# Touch.net
KiCad netlist of a schematic drawn in Altium Designer
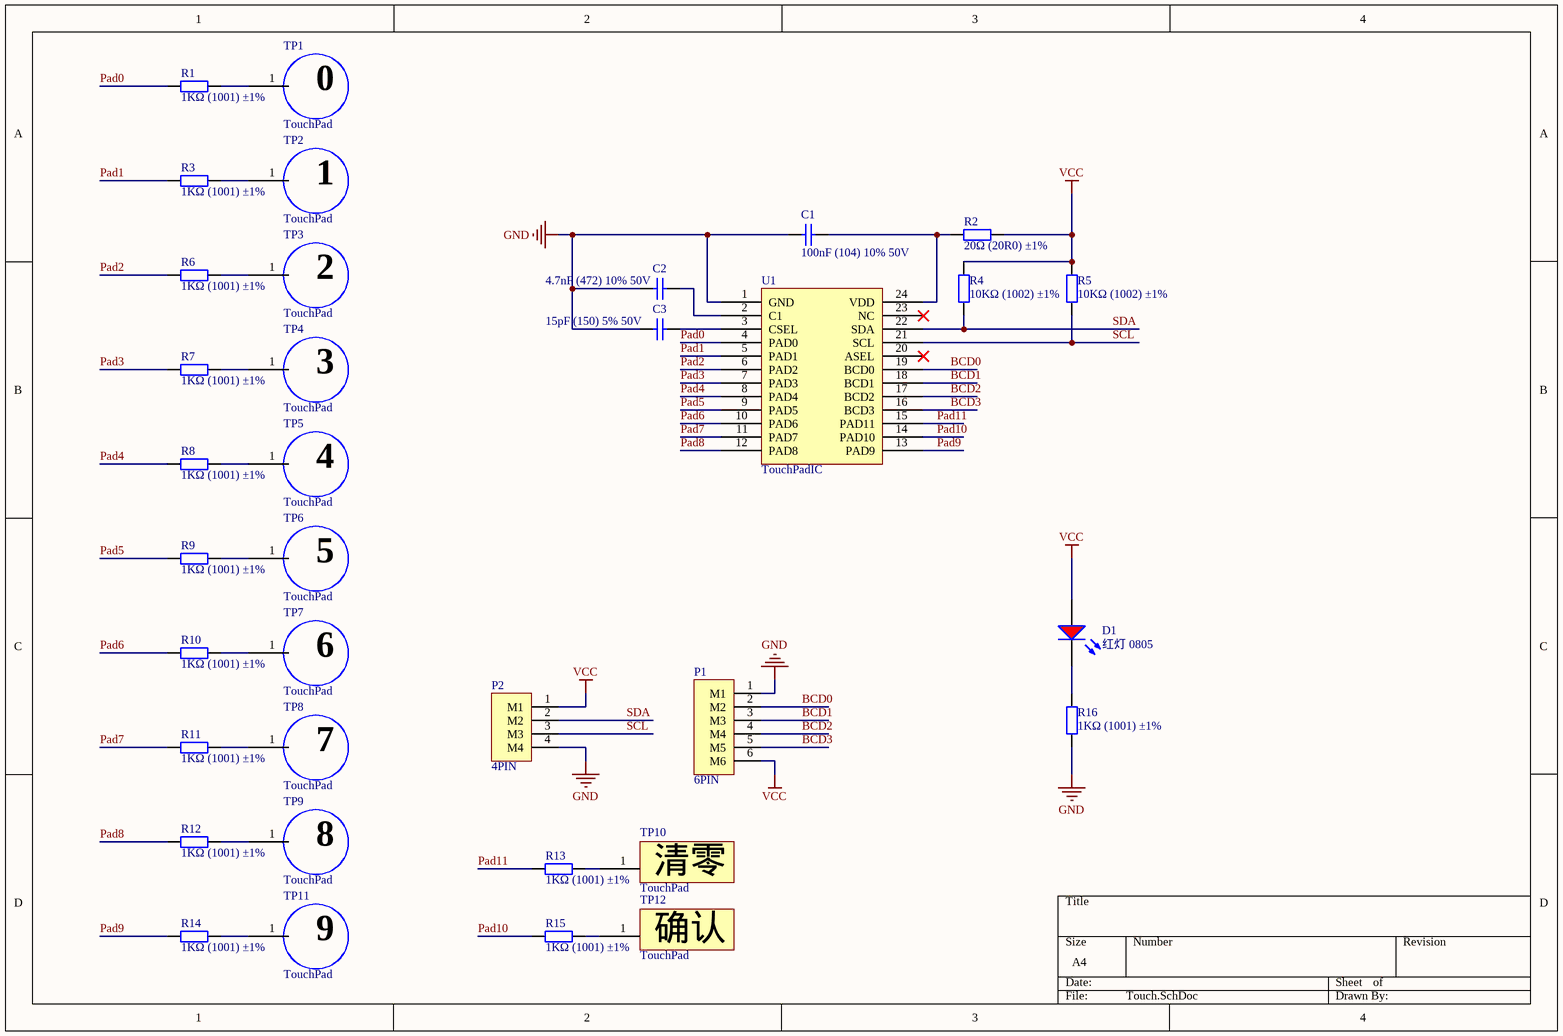
[diagram p0: Touch.SchDoc]

(export (version "E")
  (design (tool "Eeschema 10.0.6"))
  (components
    (comp (ref "C1")
      (value "100nF (104) 10% 50V")
      (footprint "0603_C")
      (description "贴片电容")
      (libsource (lib "Cap") (part "0603 100nF (104) 10% 50V"))
    )
    (comp (ref "C2")
      (value "4.7nF (472) 10% 50V")
      (footprint "0603_C")
      (description "贴片电容")
      (libsource (lib "Cap") (part "0603 4.7nF (472) 10% 50V"))
    )
    (comp (ref "C3")
      (value "15pF (150) 5% 50V")
      (footprint "0603_C")
      (description "贴片电容")
      (libsource (lib "Cap") (part "0603 15pF (150) 5% 50V"))
    )
    (comp (ref "D1")
      (value "红灯 0805")
      (footprint "0805_LED_S1")
      (description "发光二极管")
      (libsource (lib "LED") (part "0805 红灯"))
    )
    (comp (ref "P1") (value "6PIN") (footprint "MX1.25WS-6P") (libsource (lib "集大电协1.5") (part "接线端子-6PIN")))
    (comp (ref "P2") (value "4PIN") (footprint "PH2.0WS-4P") (libsource (lib "集大电协1.5") (part "接线端子-4PIN")))
    (comp (ref "R1")
      (value "1KΩ (1001) ±1%")
      (footprint "0603_R")
      (description "贴片电阻")
      (libsource (lib "RES") (part "0603 1KΩ (1001) 1%"))
    )
    (comp (ref "R2")
      (value "20Ω (20R0) ±1%")
      (footprint "0603_R")
      (description "贴片电阻")
      (libsource (lib "RES") (part "0603 20Ω (20R0) 1%"))
    )
    (comp (ref "R3")
      (value "1KΩ (1001) ±1%")
      (footprint "0603_R")
      (description "贴片电阻")
      (libsource (lib "RES") (part "0603 1KΩ (1001) 1%"))
    )
    (comp (ref "R4")
      (value "10KΩ (1002) ±1%")
      (footprint "0603_R")
      (description "贴片电阻")
      (libsource (lib "RES") (part "0603 10KΩ (1002) 1%"))
    )
    (comp (ref "R5")
      (value "10KΩ (1002) ±1%")
      (footprint "0603_R")
      (description "贴片电阻")
      (libsource (lib "RES") (part "0603 10KΩ (1002) 1%"))
    )
    (comp (ref "R6")
      (value "1KΩ (1001) ±1%")
      (footprint "0603_R")
      (description "贴片电阻")
      (libsource (lib "RES") (part "0603 1KΩ (1001) 1%"))
    )
    (comp (ref "R7")
      (value "1KΩ (1001) ±1%")
      (footprint "0603_R")
      (description "贴片电阻")
      (libsource (lib "RES") (part "0603 1KΩ (1001) 1%"))
    )
    (comp (ref "R8")
      (value "1KΩ (1001) ±1%")
      (footprint "0603_R")
      (description "贴片电阻")
      (libsource (lib "RES") (part "0603 1KΩ (1001) 1%"))
    )
    (comp (ref "R9")
      (value "1KΩ (1001) ±1%")
      (footprint "0603_R")
      (description "贴片电阻")
      (libsource (lib "RES") (part "0603 1KΩ (1001) 1%"))
    )
    (comp (ref "R10")
      (value "1KΩ (1001) ±1%")
      (footprint "0603_R")
      (description "贴片电阻")
      (libsource (lib "RES") (part "0603 1KΩ (1001) 1%"))
    )
    (comp (ref "R11")
      (value "1KΩ (1001) ±1%")
      (footprint "0603_R")
      (description "贴片电阻")
      (libsource (lib "RES") (part "0603 1KΩ (1001) 1%"))
    )
    (comp (ref "R12")
      (value "1KΩ (1001) ±1%")
      (footprint "0603_R")
      (description "贴片电阻")
      (libsource (lib "RES") (part "0603 1KΩ (1001) 1%"))
    )
    (comp (ref "R13")
      (value "1KΩ (1001) ±1%")
      (footprint "0603_R")
      (description "贴片电阻")
      (libsource (lib "RES") (part "0603 1KΩ (1001) 1%"))
    )
    (comp (ref "R14")
      (value "1KΩ (1001) ±1%")
      (footprint "0603_R")
      (description "贴片电阻")
      (libsource (lib "RES") (part "0603 1KΩ (1001) 1%"))
    )
    (comp (ref "R15")
      (value "1KΩ (1001) ±1%")
      (footprint "0603_R")
      (description "贴片电阻")
      (libsource (lib "RES") (part "0603 1KΩ (1001) 1%"))
    )
    (comp (ref "R16")
      (value "1KΩ (1001) ±1%")
      (footprint "0603_R")
      (description "贴片电阻")
      (libsource (lib "") (part "0603 1KΩ (1001) 1%_1"))
    )
    (comp (ref "TP1") (value "TouchPad") (footprint "KEY0") (libsource (lib "Schlib2") (part "Touch0")))
    (comp (ref "TP2") (value "TouchPad") (footprint "Key1") (libsource (lib "Schlib2") (part "Touch1")))
    (comp (ref "TP3") (value "TouchPad") (footprint "Key2") (libsource (lib "Schlib2") (part "Touch2")))
    (comp (ref "TP4") (value "TouchPad") (footprint "Key3") (libsource (lib "Schlib2") (part "Touch3")))
    (comp (ref "TP5") (value "TouchPad") (footprint "KEY4") (libsource (lib "Schlib2") (part "Touch4")))
    (comp (ref "TP6") (value "TouchPad") (footprint "KEY5") (libsource (lib "Schlib2") (part "Touch5")))
    (comp (ref "TP7") (value "TouchPad") (footprint "KEY6") (libsource (lib "Schlib2") (part "Touch6")))
    (comp (ref "TP8") (value "TouchPad") (footprint "KEY7") (libsource (lib "Schlib2") (part "Touch7")))
    (comp (ref "TP9") (value "TouchPad") (footprint "KEY8") (libsource (lib "Schlib2") (part "Touch8")))
    (comp (ref "TP10") (value "TouchPad") (footprint "CANCEL") (libsource (lib "Schlib2") (part "No")))
    (comp (ref "TP11") (value "TouchPad") (footprint "KEY9") (libsource (lib "Schlib2") (part "Touch9")))
    (comp (ref "TP12") (value "TouchPad") (footprint "confirm") (libsource (lib "Schlib2") (part "Yes")))
    (comp (ref "U1")
      (value "TouchPadIC")
      (footprint "SOP127P1030X264-24N")
      (libsource (lib "Schlib2") (part "XW12C"))
    )
  )
  (nets
    (net (code "1") (name "/BCD0") (class "Default")
      (node (ref "P1") (pin "2") (pinfunction "M2_2") (pintype "passive"))
      (node (ref "U1") (pin "19") (pinfunction "BCD0_19") (pintype "passive"))
    )
    (net (code "2") (name "/BCD1") (class "Default")
      (node (ref "P1") (pin "3") (pinfunction "M3_3") (pintype "passive"))
      (node (ref "U1") (pin "18") (pinfunction "BCD1_18") (pintype "passive"))
    )
    (net (code "3") (name "/BCD2") (class "Default")
      (node (ref "P1") (pin "4") (pinfunction "M4_4") (pintype "passive"))
      (node (ref "U1") (pin "17") (pinfunction "BCD2_17") (pintype "passive"))
    )
    (net (code "4") (name "/BCD3") (class "Default")
      (node (ref "P1") (pin "5") (pinfunction "M5_5") (pintype "passive"))
      (node (ref "U1") (pin "16") (pinfunction "BCD3_16") (pintype "passive"))
    )
    (net (code "5") (name "/Pad0") (class "Default")
      (node (ref "R1") (pin "1") (pinfunction "1_1") (pintype "passive"))
      (node (ref "U1") (pin "4") (pinfunction "PAD0_4") (pintype "passive"))
    )
    (net (code "6") (name "/Pad1") (class "Default")
      (node (ref "R3") (pin "1") (pinfunction "1_1") (pintype "passive"))
      (node (ref "U1") (pin "5") (pinfunction "PAD1_5") (pintype "passive"))
    )
    (net (code "7") (name "/Pad2") (class "Default")
      (node (ref "R6") (pin "1") (pinfunction "1_1") (pintype "passive"))
      (node (ref "U1") (pin "6") (pinfunction "PAD2_6") (pintype "passive"))
    )
    (net (code "8") (name "/Pad3") (class "Default")
      (node (ref "R7") (pin "1") (pinfunction "1_1") (pintype "passive"))
      (node (ref "U1") (pin "7") (pinfunction "PAD3_7") (pintype "passive"))
    )
    (net (code "9") (name "/Pad4") (class "Default")
      (node (ref "R8") (pin "1") (pinfunction "1_1") (pintype "passive"))
      (node (ref "U1") (pin "8") (pinfunction "PAD4_8") (pintype "passive"))
    )
    (net (code "10") (name "/Pad5") (class "Default")
      (node (ref "R9") (pin "1") (pinfunction "1_1") (pintype "passive"))
      (node (ref "U1") (pin "9") (pinfunction "PAD5_9") (pintype "passive"))
    )
    (net (code "11") (name "/Pad6") (class "Default")
      (node (ref "R10") (pin "1") (pinfunction "1_1") (pintype "passive"))
      (node (ref "U1") (pin "10") (pinfunction "PAD6_10") (pintype "passive"))
    )
    (net (code "12") (name "/Pad7") (class "Default")
      (node (ref "R11") (pin "1") (pinfunction "1_1") (pintype "passive"))
      (node (ref "U1") (pin "11") (pinfunction "PAD7_11") (pintype "passive"))
    )
    (net (code "13") (name "/Pad8") (class "Default")
      (node (ref "R12") (pin "1") (pinfunction "1_1") (pintype "passive"))
      (node (ref "U1") (pin "12") (pinfunction "PAD8_12") (pintype "passive"))
    )
    (net (code "14") (name "/Pad9") (class "Default")
      (node (ref "R14") (pin "1") (pinfunction "1_1") (pintype "passive"))
      (node (ref "U1") (pin "13") (pinfunction "PAD9_13") (pintype "passive"))
    )
    (net (code "15") (name "/Pad10") (class "Default")
      (node (ref "R15") (pin "1") (pinfunction "1_1") (pintype "passive"))
      (node (ref "U1") (pin "14") (pinfunction "PAD10_14") (pintype "passive"))
    )
    (net (code "16") (name "/Pad11") (class "Default")
      (node (ref "R13") (pin "1") (pinfunction "1_1") (pintype "passive"))
      (node (ref "U1") (pin "15") (pinfunction "PAD11_15") (pintype "passive"))
    )
    (net (code "17") (name "/SCL") (class "Default")
      (node (ref "P2") (pin "3") (pinfunction "M3_3") (pintype "passive"))
      (node (ref "R5") (pin "1") (pinfunction "1_1") (pintype "passive"))
      (node (ref "U1") (pin "21") (pinfunction "SCL_21") (pintype "passive"))
    )
    (net (code "18") (name "/SDA") (class "Default")
      (node (ref "P2") (pin "2") (pinfunction "M2_2") (pintype "passive"))
      (node (ref "R4") (pin "1") (pinfunction "1_1") (pintype "passive"))
      (node (ref "U1") (pin "22") (pinfunction "SDA_22") (pintype "passive"))
    )
    (net (code "19") (name "GND") (class "Default")
      (node (ref "C1") (pin "1") (pinfunction "1_1") (pintype "passive"))
      (node (ref "C2") (pin "1") (pinfunction "1_1") (pintype "passive"))
      (node (ref "C3") (pin "2") (pinfunction "2_2") (pintype "passive"))
      (node (ref "P1") (pin "1") (pinfunction "M1_1") (pintype "passive"))
      (node (ref "P2") (pin "4") (pinfunction "M4_4") (pintype "passive"))
      (node (ref "R16") (pin "1") (pinfunction "1_1") (pintype "passive"))
      (node (ref "U1") (pin "1") (pinfunction "GND_1") (pintype "passive"))
    )
    (net (code "20") (name "Net-(D1-PadK)") (class "Default")
      (node (ref "D1") (pin "K") (pinfunction "K_K") (pintype "passive"))
      (node (ref "R16") (pin "2") (pinfunction "2_2") (pintype "passive"))
    )
    (net (code "21") (name "Net-(R1-Pad2)") (class "Default")
      (node (ref "R1") (pin "2") (pinfunction "2_2") (pintype "passive"))
      (node (ref "TP1") (pin "1") (pinfunction "1_1") (pintype "passive"))
    )
    (net (code "22") (name "Net-(R3-Pad2)") (class "Default")
      (node (ref "R3") (pin "2") (pinfunction "2_2") (pintype "passive"))
      (node (ref "TP2") (pin "1") (pinfunction "1_1") (pintype "passive"))
    )
    (net (code "23") (name "Net-(R6-Pad2)") (class "Default")
      (node (ref "R6") (pin "2") (pinfunction "2_2") (pintype "passive"))
      (node (ref "TP3") (pin "1") (pinfunction "1_1") (pintype "passive"))
    )
    (net (code "24") (name "Net-(R7-Pad2)") (class "Default")
      (node (ref "R7") (pin "2") (pinfunction "2_2") (pintype "passive"))
      (node (ref "TP4") (pin "1") (pinfunction "1_1") (pintype "passive"))
    )
    (net (code "25") (name "Net-(R8-Pad2)") (class "Default")
      (node (ref "R8") (pin "2") (pinfunction "2_2") (pintype "passive"))
      (node (ref "TP5") (pin "1") (pinfunction "1_1") (pintype "passive"))
    )
    (net (code "26") (name "Net-(R9-Pad2)") (class "Default")
      (node (ref "R9") (pin "2") (pinfunction "2_2") (pintype "passive"))
      (node (ref "TP6") (pin "1") (pinfunction "1_1") (pintype "passive"))
    )
    (net (code "27") (name "Net-(R10-Pad2)") (class "Default")
      (node (ref "R10") (pin "2") (pinfunction "2_2") (pintype "passive"))
      (node (ref "TP7") (pin "1") (pinfunction "1_1") (pintype "passive"))
    )
    (net (code "28") (name "Net-(R11-Pad2)") (class "Default")
      (node (ref "R11") (pin "2") (pinfunction "2_2") (pintype "passive"))
      (node (ref "TP8") (pin "1") (pinfunction "1_1") (pintype "passive"))
    )
    (net (code "29") (name "Net-(R12-Pad2)") (class "Default")
      (node (ref "R12") (pin "2") (pinfunction "2_2") (pintype "passive"))
      (node (ref "TP9") (pin "1") (pinfunction "1_1") (pintype "passive"))
    )
    (net (code "30") (name "Net-(R13-Pad2)") (class "Default")
      (node (ref "R13") (pin "2") (pinfunction "2_2") (pintype "passive"))
      (node (ref "TP10") (pin "1") (pinfunction "1_1") (pintype "passive"))
    )
    (net (code "31") (name "Net-(R14-Pad2)") (class "Default")
      (node (ref "R14") (pin "2") (pinfunction "2_2") (pintype "passive"))
      (node (ref "TP11") (pin "1") (pinfunction "1_1") (pintype "passive"))
    )
    (net (code "32") (name "Net-(R15-Pad2)") (class "Default")
      (node (ref "R15") (pin "2") (pinfunction "2_2") (pintype "passive"))
      (node (ref "TP12") (pin "1") (pinfunction "1_1") (pintype "passive"))
    )
    (net (code "33") (name "Net-(U1-C1)") (class "Default")
      (node (ref "C2") (pin "2") (pinfunction "2_2") (pintype "passive"))
      (node (ref "U1") (pin "2") (pinfunction "C1_2") (pintype "passive"))
    )
    (net (code "34") (name "Net-(U1-CSEL)") (class "Default")
      (node (ref "C3") (pin "1") (pinfunction "1_1") (pintype "passive"))
      (node (ref "U1") (pin "3") (pinfunction "CSEL_3") (pintype "passive"))
    )
    (net (code "35") (name "Net-(U1-VDD)") (class "Default")
      (node (ref "C1") (pin "2") (pinfunction "2_2") (pintype "passive"))
      (node (ref "R2") (pin "1") (pinfunction "1_1") (pintype "passive"))
      (node (ref "U1") (pin "24") (pinfunction "VDD_24") (pintype "passive"))
    )
    (net (code "36") (name "VCC") (class "Default")
      (node (ref "D1") (pin "A") (pinfunction "A_A") (pintype "passive"))
      (node (ref "P1") (pin "6") (pinfunction "M6_6") (pintype "passive"))
      (node (ref "P2") (pin "1") (pinfunction "M1_1") (pintype "passive"))
      (node (ref "R2") (pin "2") (pinfunction "2_2") (pintype "passive"))
      (node (ref "R4") (pin "2") (pinfunction "2_2") (pintype "passive"))
      (node (ref "R5") (pin "2") (pinfunction "2_2") (pintype "passive"))
    )
    (net (code "37") (name "unconnected-(U1-ASEL-Pad20)") (class "Default")
      (node (ref "U1") (pin "20") (pinfunction "ASEL_20") (pintype "passive+no_connect"))
    )
    (net (code "38") (name "unconnected-(U1-NC-Pad23)") (class "Default")
      (node (ref "U1") (pin "23") (pinfunction "NC_23") (pintype "passive+no_connect"))
    )
  )
)
